# motor_ctrl_pw_v1.net
KiCad netlist of a schematic drawn in EAGLE
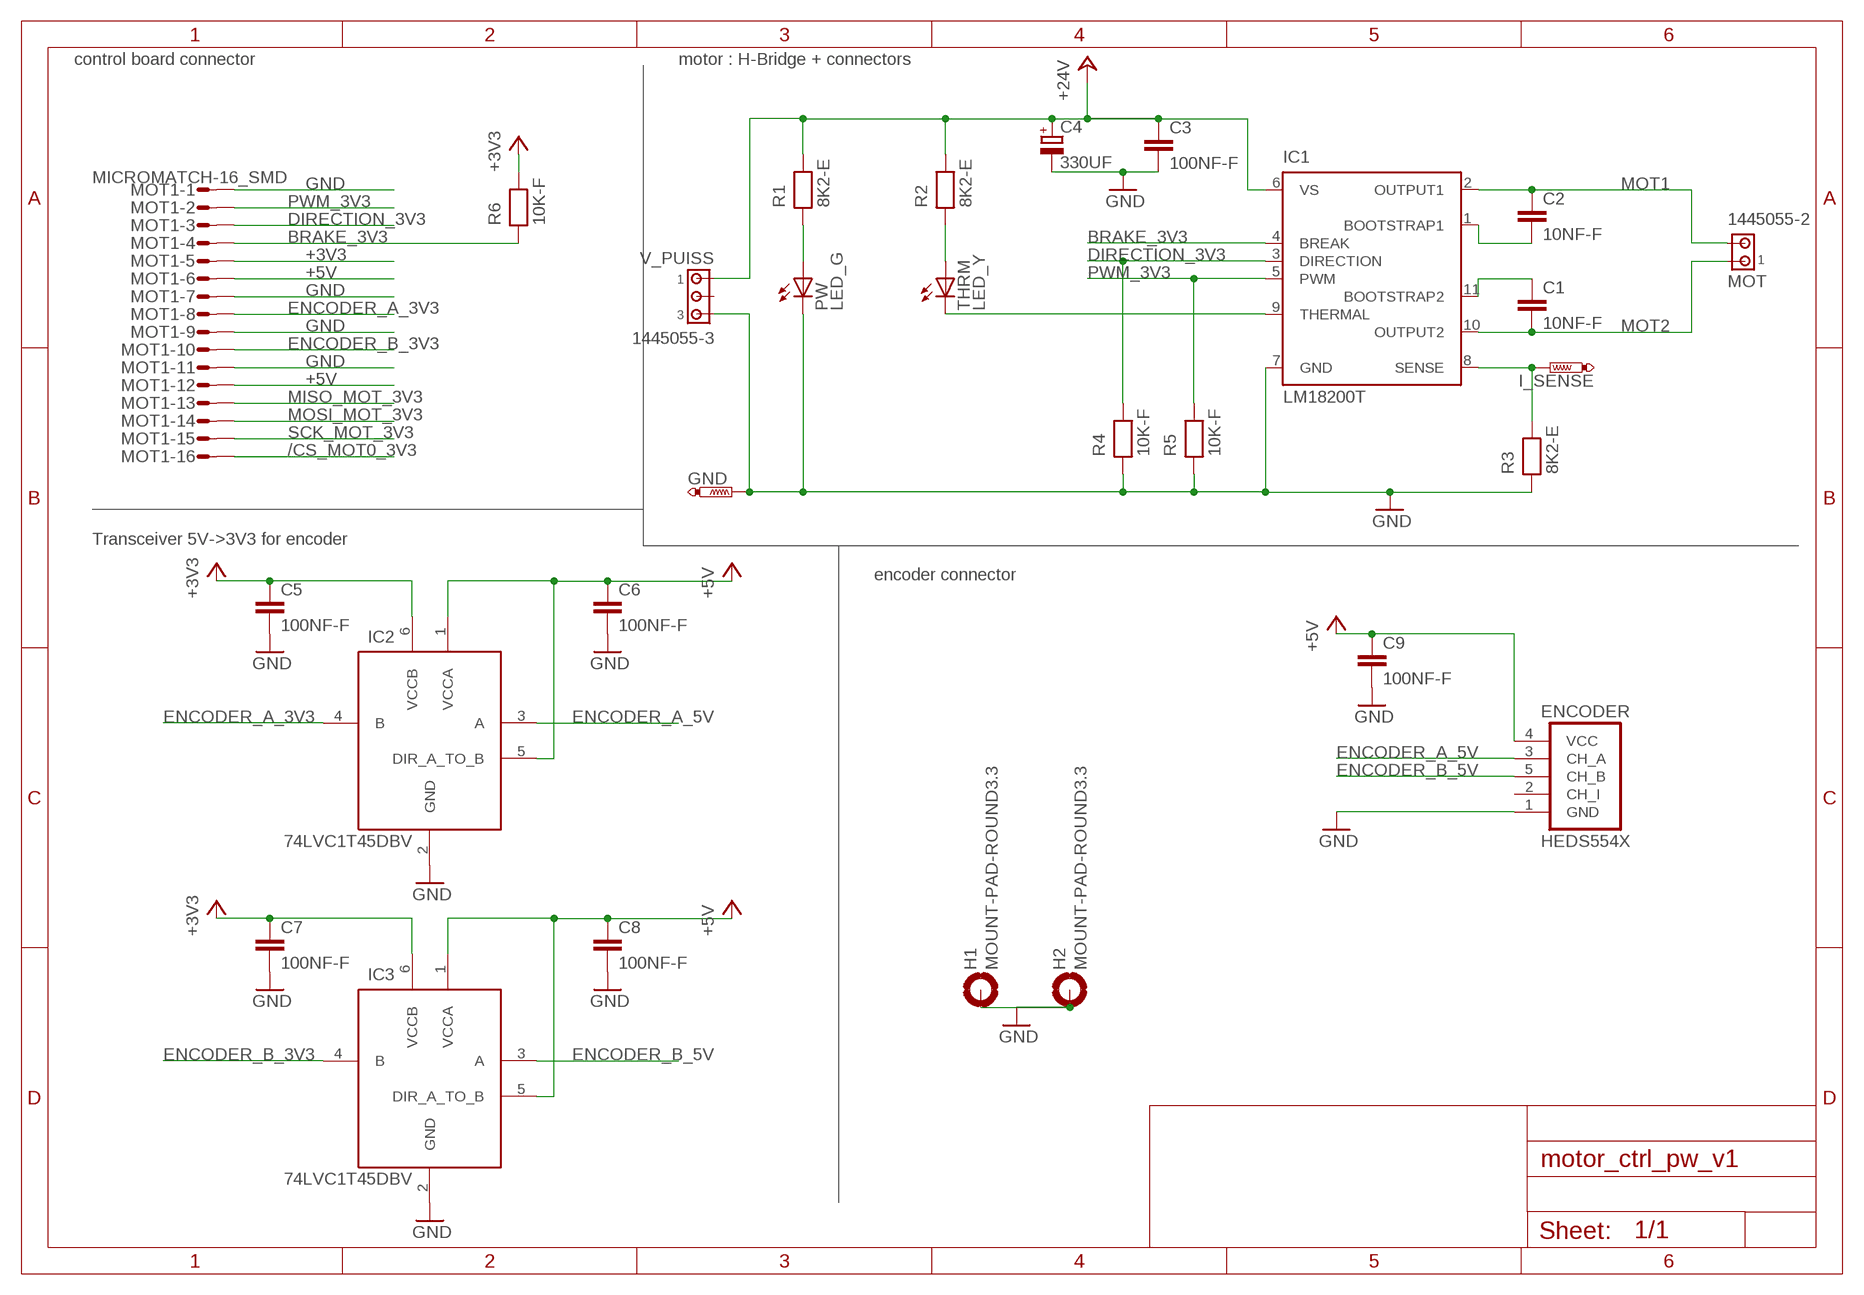
[diagram p0: schematic, sheet 1]

(export (version "E")
  (design (tool "Eeschema 10.0.6"))
  (components
    (comp (ref "C1")
      (value "10NF-F")
      (footprint "eagle-import:C0603")
      (libsource (lib "eagle-import") (part "10NF-F"))
    )
    (comp (ref "C2")
      (value "10NF-F")
      (footprint "eagle-import:C0603")
      (libsource (lib "eagle-import") (part "10NF-F"))
    )
    (comp (ref "C3")
      (value "100NF-F")
      (footprint "eagle-import:C0603")
      (libsource (lib "eagle-import") (part "100NF-F"))
    )
    (comp (ref "C4")
      (value "330UF")
      (footprint "eagle-import:PANASONIC_G")
      (fields (field (name "MANUFACTURER") "EEEFK1V331P"))
      (libsource (lib "eagle-import") (part "330UF"))
    )
    (comp (ref "C5")
      (value "100NF-F")
      (footprint "eagle-import:C0603")
      (libsource (lib "eagle-import") (part "100NF-F"))
    )
    (comp (ref "C6")
      (value "100NF-F")
      (footprint "eagle-import:C0603")
      (libsource (lib "eagle-import") (part "100NF-F"))
    )
    (comp (ref "C7")
      (value "100NF-F")
      (footprint "eagle-import:C0603")
      (libsource (lib "eagle-import") (part "100NF-F"))
    )
    (comp (ref "C8")
      (value "100NF-F")
      (footprint "eagle-import:C0603")
      (libsource (lib "eagle-import") (part "100NF-F"))
    )
    (comp (ref "C9")
      (value "100NF-F")
      (footprint "eagle-import:C0603")
      (libsource (lib "eagle-import") (part "100NF-F"))
    )
    (comp (ref "ENCODER")
      (value "HEDS554X")
      (footprint "eagle-import:22-05-1052")
      (libsource (lib "eagle-import") (part "HEDS554X"))
    )
    (comp (ref "GND")
      (value "PTR1PAD1-13")
      (footprint "eagle-import:P1-13")
      (libsource (lib "eagle-import") (part "PTR1PAD1-13"))
    )
    (comp (ref "H1")
      (value "MOUNT-PAD-ROUND3.3")
      (footprint "eagle-import:3,3-PAD")
      (libsource (lib "eagle-import") (part "MOUNT-PAD-ROUND3.3"))
    )
    (comp (ref "H2")
      (value "MOUNT-PAD-ROUND3.3")
      (footprint "eagle-import:3,3-PAD")
      (libsource (lib "eagle-import") (part "MOUNT-PAD-ROUND3.3"))
    )
    (comp (ref "IC1")
      (value "LM18200T")
      (footprint "eagle-import:TO-220-11")
      (libsource (lib "eagle-import") (part "LM18200T"))
    )
    (comp (ref "IC2")
      (value "74LVC1T45DBV")
      (footprint "eagle-import:SOT23-6")
      (libsource (lib "eagle-import") (part "74LVC1T45DBV"))
    )
    (comp (ref "IC3")
      (value "74LVC1T45DBV")
      (footprint "eagle-import:SOT23-6")
      (libsource (lib "eagle-import") (part "74LVC1T45DBV"))
    )
    (comp (ref "I_SENSE")
      (value "PTR1PAD1-13")
      (footprint "eagle-import:P1-13")
      (libsource (lib "eagle-import") (part "PTR1PAD1-13"))
    )
    (comp (ref "MOT")
      (value "1445055-2")
      (footprint "eagle-import:1445055-2")
      (libsource (lib "eagle-import") (part "1445055-2"))
    )
    (comp (ref "MOT1")
      (value "MICROMATCH-16_SMD")
      (footprint "eagle-import:MICROMATCH-16_SMD")
      (libsource (lib "eagle-import") (part "MICROMATCH-16_SMD"))
    )
    (comp (ref "PW")
      (value "LED_G")
      (footprint "eagle-import:CHIP-LED0805")
      (libsource (lib "eagle-import") (part "LED_G"))
    )
    (comp (ref "R1")
      (value "8K2-E")
      (footprint "eagle-import:R0805")
      (libsource (lib "eagle-import") (part "8K2-E"))
    )
    (comp (ref "R2")
      (value "8K2-E")
      (footprint "eagle-import:R0805")
      (libsource (lib "eagle-import") (part "8K2-E"))
    )
    (comp (ref "R3")
      (value "8K2-E")
      (footprint "eagle-import:R0805")
      (libsource (lib "eagle-import") (part "8K2-E"))
    )
    (comp (ref "R4")
      (value "10K-F")
      (footprint "eagle-import:R0603")
      (libsource (lib "eagle-import") (part "10K-F"))
    )
    (comp (ref "R5")
      (value "10K-F")
      (footprint "eagle-import:R0603")
      (libsource (lib "eagle-import") (part "10K-F"))
    )
    (comp (ref "R6")
      (value "10K-F")
      (footprint "eagle-import:R0603")
      (libsource (lib "eagle-import") (part "10K-F"))
    )
    (comp (ref "THRM")
      (value "LED_Y")
      (footprint "eagle-import:CHIP-LED0805")
      (libsource (lib "eagle-import") (part "LED_Y"))
    )
    (comp (ref "V_PUISS")
      (value "1445055-3")
      (footprint "eagle-import:1445055-3")
      (libsource (lib "eagle-import") (part "1445055-3"))
    )
  )
  (nets
    (net (code "1") (name "+3V3") (class "Default")
      (node (ref "C5") (pin "1") (pinfunction "1_1") (pintype "passive"))
      (node (ref "C7") (pin "1") (pinfunction "1_1") (pintype "passive"))
      (node (ref "IC2") (pin "6") (pinfunction "VCCB_6") (pintype "power_in"))
      (node (ref "IC3") (pin "6") (pinfunction "VCCB_6") (pintype "power_in"))
      (node (ref "MOT1") (pin "5") (pinfunction "S_5") (pintype "passive"))
      (node (ref "R6") (pin "2") (pinfunction "2_2") (pintype "bidirectional"))
    )
    (net (code "2") (name "+5V") (class "Default")
      (node (ref "C6") (pin "1") (pinfunction "1_1") (pintype "passive"))
      (node (ref "C8") (pin "1") (pinfunction "1_1") (pintype "passive"))
      (node (ref "C9") (pin "1") (pinfunction "1_1") (pintype "passive"))
      (node (ref "ENCODER") (pin "4") (pinfunction "VCC_4") (pintype "passive"))
      (node (ref "IC2") (pin "1") (pinfunction "VCCA_1") (pintype "power_in"))
      (node (ref "IC2") (pin "5") (pinfunction "DIR_A_TO_B_5") (pintype "bidirectional"))
      (node (ref "IC3") (pin "1") (pinfunction "VCCA_1") (pintype "power_in"))
      (node (ref "IC3") (pin "5") (pinfunction "DIR_A_TO_B_5") (pintype "bidirectional"))
      (node (ref "MOT1") (pin "12") (pinfunction "S_12") (pintype "passive"))
      (node (ref "MOT1") (pin "6") (pinfunction "S_6") (pintype "passive"))
    )
    (net (code "3") (name "+24V") (class "Default")
      (node (ref "C3") (pin "1") (pinfunction "1_1") (pintype "passive"))
      (node (ref "C4") (pin "+") (pinfunction "+_+") (pintype "passive"))
      (node (ref "IC1") (pin "6") (pinfunction "VS_6") (pintype "power_in"))
      (node (ref "R1") (pin "2") (pinfunction "2_2") (pintype "bidirectional"))
      (node (ref "R2") (pin "2") (pinfunction "2_2") (pintype "bidirectional"))
      (node (ref "V_PUISS") (pin "1") (pinfunction "1_1") (pintype "passive"))
    )
    (net (code "4") (name "/BRAKE_3V3") (class "Default")
      (node (ref "IC1") (pin "4") (pinfunction "BREAK_4") (pintype "input"))
      (node (ref "MOT1") (pin "4") (pinfunction "S_4") (pintype "passive"))
      (node (ref "R6") (pin "1") (pinfunction "1_1") (pintype "bidirectional"))
    )
    (net (code "5") (name "/DIRECTION_3V3") (class "Default")
      (node (ref "IC1") (pin "3") (pinfunction "DIRECTION_3") (pintype "input"))
      (node (ref "MOT1") (pin "3") (pinfunction "S_3") (pintype "passive"))
      (node (ref "R4") (pin "2") (pinfunction "2_2") (pintype "bidirectional"))
    )
    (net (code "6") (name "/ENCODER_A_3V3") (class "Default")
      (node (ref "IC2") (pin "4") (pinfunction "B_4") (pintype "bidirectional"))
      (node (ref "MOT1") (pin "8") (pinfunction "S_8") (pintype "passive"))
    )
    (net (code "7") (name "/ENCODER_A_5V") (class "Default")
      (node (ref "ENCODER") (pin "3") (pinfunction "CH_A_3") (pintype "passive"))
      (node (ref "IC2") (pin "3") (pinfunction "A_3") (pintype "bidirectional"))
    )
    (net (code "8") (name "/ENCODER_B_3V3") (class "Default")
      (node (ref "IC3") (pin "4") (pinfunction "B_4") (pintype "bidirectional"))
      (node (ref "MOT1") (pin "10") (pinfunction "S_10") (pintype "passive"))
    )
    (net (code "9") (name "/ENCODER_B_5V") (class "Default")
      (node (ref "ENCODER") (pin "5") (pinfunction "CH_B_5") (pintype "passive"))
      (node (ref "IC3") (pin "3") (pinfunction "A_3") (pintype "bidirectional"))
    )
    (net (code "10") (name "/MISO_MOT_3V3") (class "Default")
      (node (ref "MOT1") (pin "13") (pinfunction "S_13") (pintype "passive"))
    )
    (net (code "11") (name "/MOSI_MOT_3V3") (class "Default")
      (node (ref "MOT1") (pin "14") (pinfunction "S_14") (pintype "passive"))
    )
    (net (code "12") (name "/MOT1") (class "Default")
      (node (ref "C2") (pin "1") (pinfunction "1_1") (pintype "passive"))
      (node (ref "IC1") (pin "2") (pinfunction "OUTPUT1_2") (pintype "output"))
      (node (ref "MOT") (pin "2") (pinfunction "2_2") (pintype "passive"))
    )
    (net (code "13") (name "/MOT2") (class "Default")
      (node (ref "C1") (pin "2") (pinfunction "2_2") (pintype "passive"))
      (node (ref "IC1") (pin "10") (pinfunction "OUTPUT2_10") (pintype "output"))
      (node (ref "MOT") (pin "1") (pinfunction "1_1") (pintype "passive"))
    )
    (net (code "14") (name "/PWM_3V3") (class "Default")
      (node (ref "IC1") (pin "5") (pinfunction "PWM_5") (pintype "input"))
      (node (ref "MOT1") (pin "2") (pinfunction "S_2") (pintype "passive"))
      (node (ref "R5") (pin "2") (pinfunction "2_2") (pintype "bidirectional"))
    )
    (net (code "15") (name "/SCK_MOT_3V3") (class "Default")
      (node (ref "MOT1") (pin "15") (pinfunction "S_15") (pintype "passive"))
    )
    (net (code "16") (name "/{slash}CS_MOT0_3V3") (class "Default")
      (node (ref "MOT1") (pin "16") (pinfunction "S_16") (pintype "passive"))
    )
    (net (code "17") (name "GND") (class "Default")
      (node (ref "C3") (pin "2") (pinfunction "2_2") (pintype "passive"))
      (node (ref "C4") (pin "-") (pinfunction "-_-") (pintype "passive"))
      (node (ref "C5") (pin "2") (pinfunction "2_2") (pintype "passive"))
      (node (ref "C6") (pin "2") (pinfunction "2_2") (pintype "passive"))
      (node (ref "C7") (pin "2") (pinfunction "2_2") (pintype "passive"))
      (node (ref "C8") (pin "2") (pinfunction "2_2") (pintype "passive"))
      (node (ref "C9") (pin "2") (pinfunction "2_2") (pintype "passive"))
      (node (ref "ENCODER") (pin "1") (pinfunction "GND_1") (pintype "passive"))
      (node (ref "GND") (pin "TP") (pinfunction "TP_TP") (pintype "input"))
      (node (ref "H1") (pin "B3,3") (pinfunction "MOUNT_B3,3") (pintype "passive"))
      (node (ref "H2") (pin "B3,3") (pinfunction "MOUNT_B3,3") (pintype "passive"))
      (node (ref "IC1") (pin "7") (pinfunction "GND_7") (pintype "power_in"))
      (node (ref "IC2") (pin "2") (pinfunction "GND_2") (pintype "power_in"))
      (node (ref "IC3") (pin "2") (pinfunction "GND_2") (pintype "power_in"))
      (node (ref "MOT1") (pin "1") (pinfunction "S_1") (pintype "passive"))
      (node (ref "MOT1") (pin "11") (pinfunction "S_11") (pintype "passive"))
      (node (ref "MOT1") (pin "7") (pinfunction "S_7") (pintype "passive"))
      (node (ref "MOT1") (pin "9") (pinfunction "S_9") (pintype "passive"))
      (node (ref "PW") (pin "C") (pinfunction "C_C") (pintype "passive"))
      (node (ref "R3") (pin "1") (pinfunction "1_1") (pintype "bidirectional"))
      (node (ref "R4") (pin "1") (pinfunction "1_1") (pintype "bidirectional"))
      (node (ref "R5") (pin "1") (pinfunction "1_1") (pintype "bidirectional"))
      (node (ref "V_PUISS") (pin "3") (pinfunction "3_3") (pintype "passive"))
    )
    (net (code "18") (name "Net-(IC1-BOOTSTRAP1)") (class "Default")
      (node (ref "C2") (pin "2") (pinfunction "2_2") (pintype "passive"))
      (node (ref "IC1") (pin "1") (pinfunction "BOOTSTRAP1_1") (pintype "input"))
    )
    (net (code "19") (name "Net-(IC1-BOOTSTRAP2)") (class "Default")
      (node (ref "C1") (pin "1") (pinfunction "1_1") (pintype "passive"))
      (node (ref "IC1") (pin "11") (pinfunction "BOOTSTRAP2_11") (pintype "input"))
    )
    (net (code "20") (name "Net-(IC1-SENSE)") (class "Default")
      (node (ref "IC1") (pin "8") (pinfunction "SENSE_8") (pintype "output"))
      (node (ref "I_SENSE") (pin "TP") (pinfunction "TP_TP") (pintype "input"))
      (node (ref "R3") (pin "2") (pinfunction "2_2") (pintype "bidirectional"))
    )
    (net (code "21") (name "Net-(IC1-THERMAL)") (class "Default")
      (node (ref "IC1") (pin "9") (pinfunction "THERMAL_9") (pintype "output"))
      (node (ref "THRM") (pin "C") (pinfunction "C_C") (pintype "passive"))
    )
    (net (code "22") (name "Net-(PW-PadA)") (class "Default")
      (node (ref "PW") (pin "A") (pinfunction "A_A") (pintype "passive"))
      (node (ref "R1") (pin "1") (pinfunction "1_1") (pintype "bidirectional"))
    )
    (net (code "23") (name "Net-(R2-Pad1)") (class "Default")
      (node (ref "R2") (pin "1") (pinfunction "1_1") (pintype "bidirectional"))
      (node (ref "THRM") (pin "A") (pinfunction "A_A") (pintype "passive"))
    )
    (net (code "24") (name "unconnected-(ENCODER-CH_I-Pad2)") (class "Default")
      (node (ref "ENCODER") (pin "2") (pinfunction "CH_I_2") (pintype "passive"))
    )
    (net (code "25") (name "unconnected-(V_PUISS-Pad2)") (class "Default")
      (node (ref "V_PUISS") (pin "2") (pinfunction "2_2") (pintype "passive"))
    )
  )
)
